# FilamentRecycle.net
KiCad netlist of a schematic drawn in EAGLE
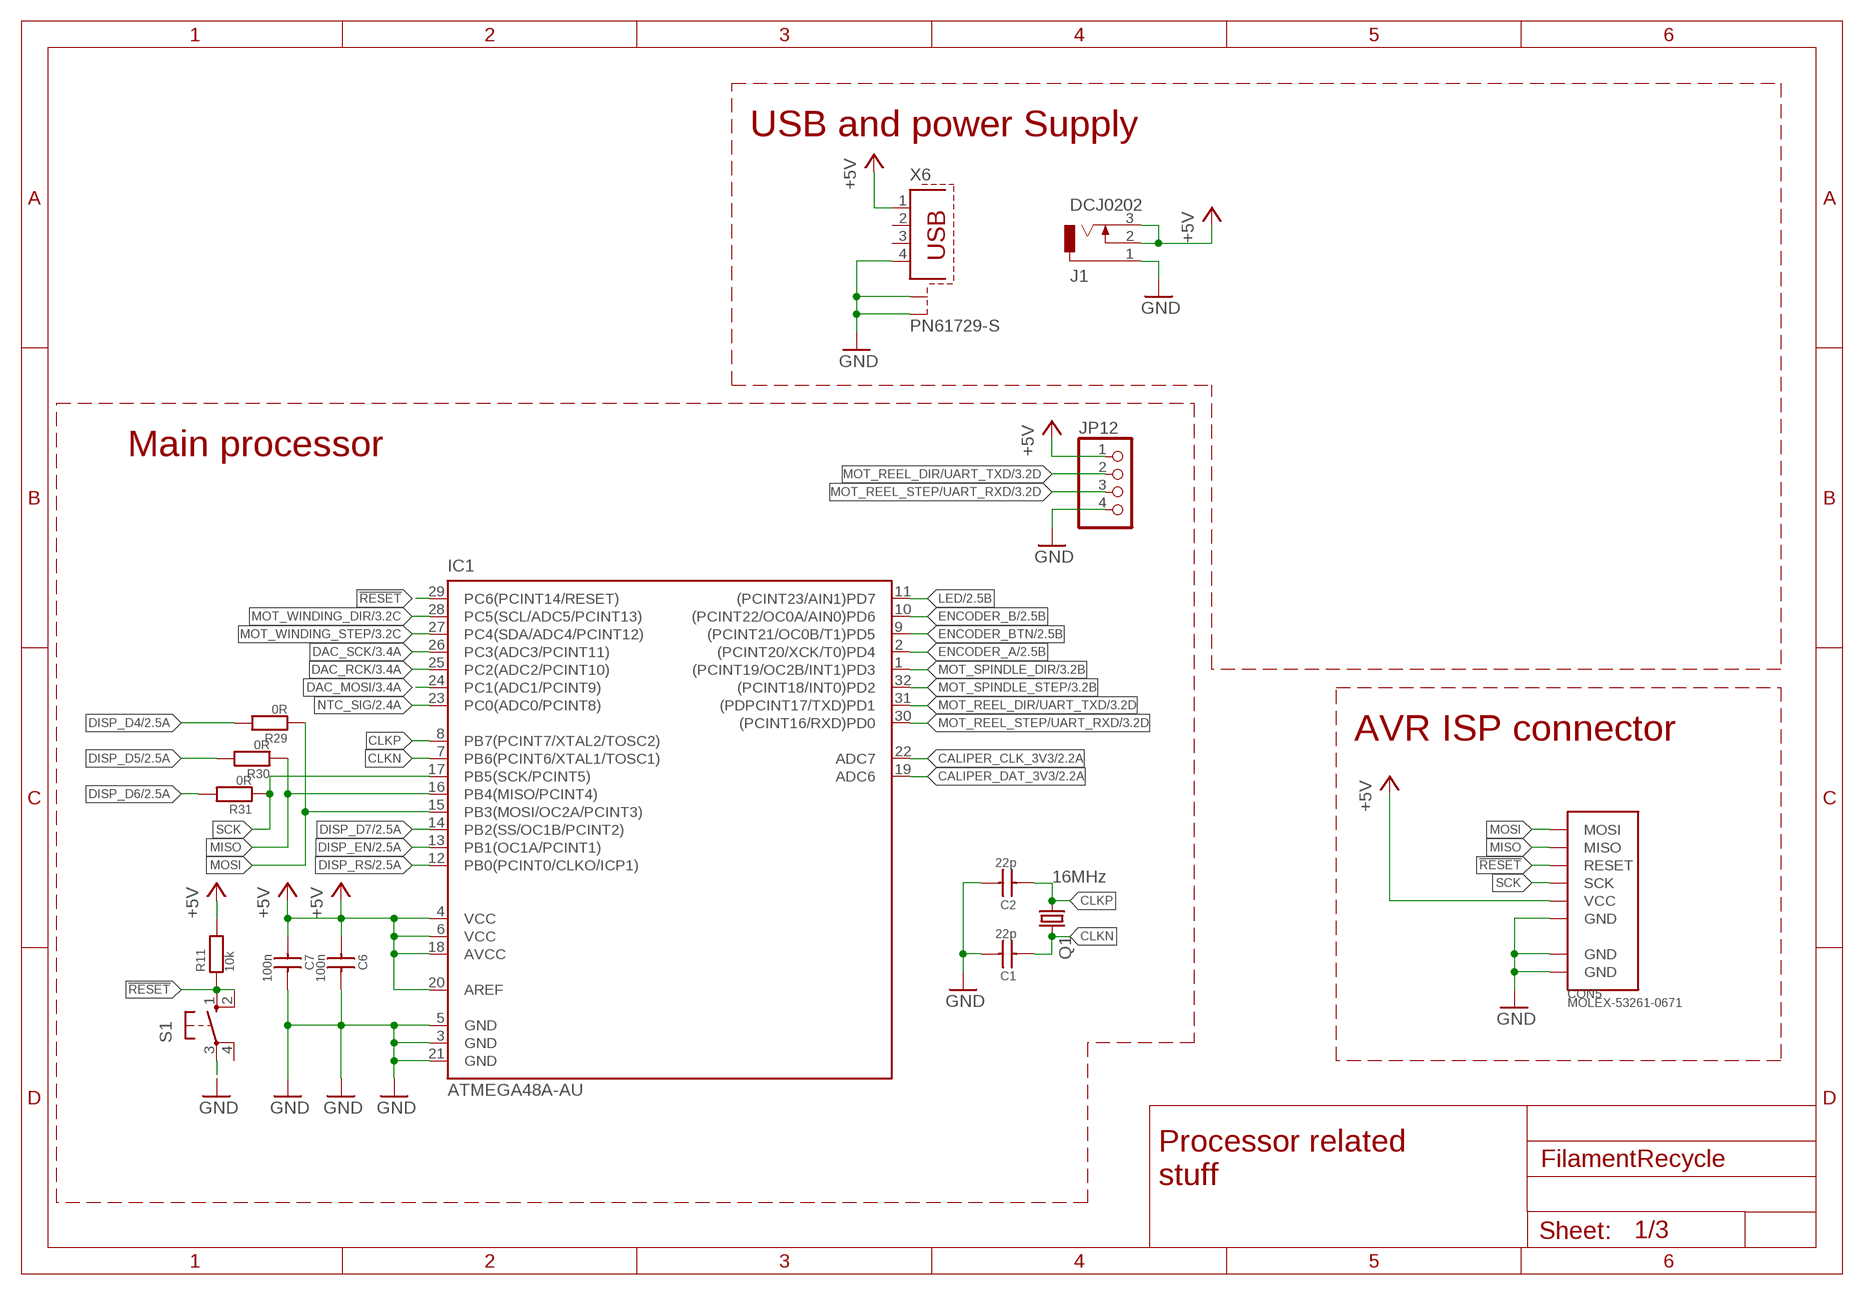
[diagram p0: schematic, sheet 1]
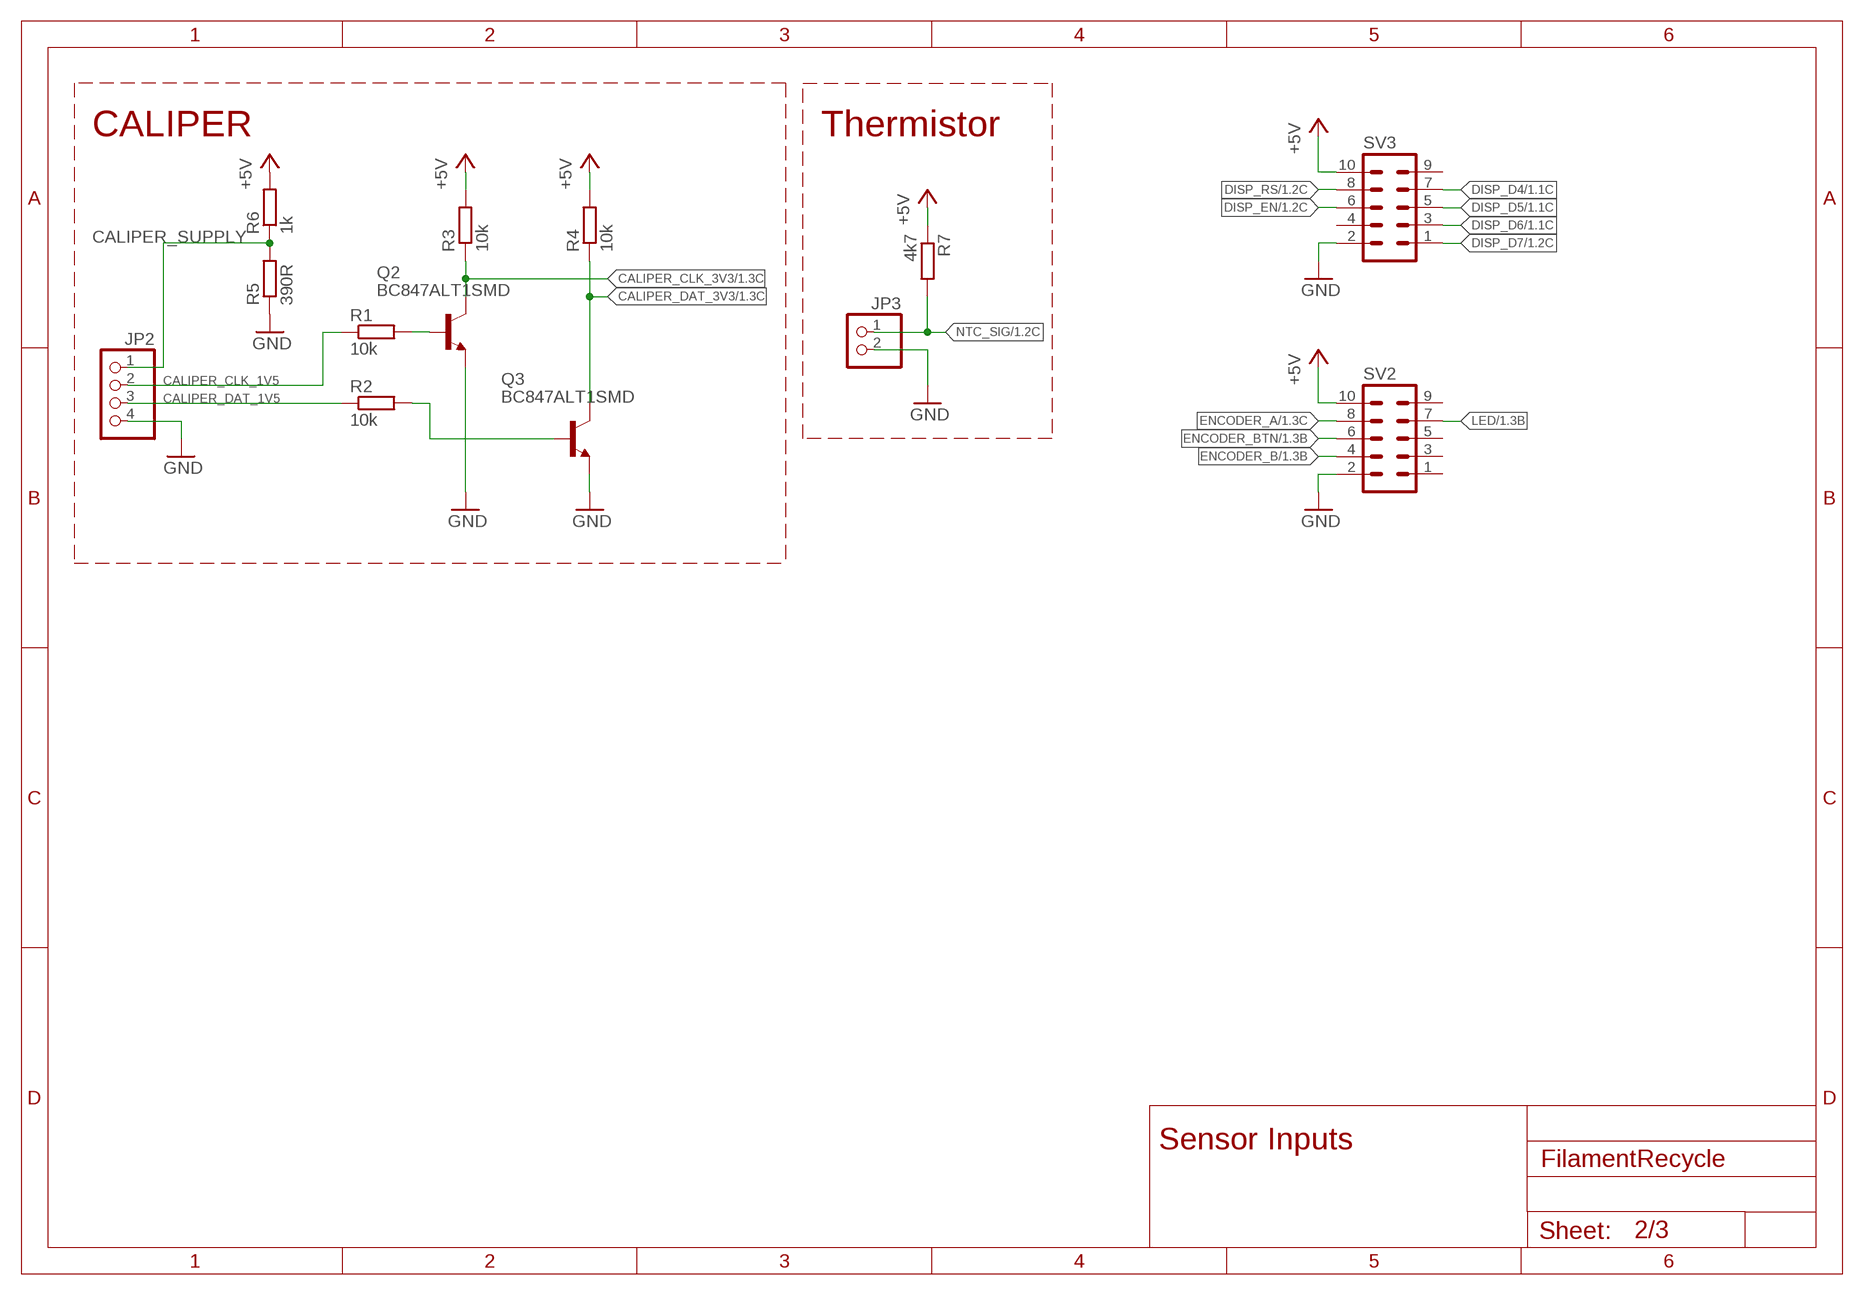
[diagram p1: schematic, sheet 2]
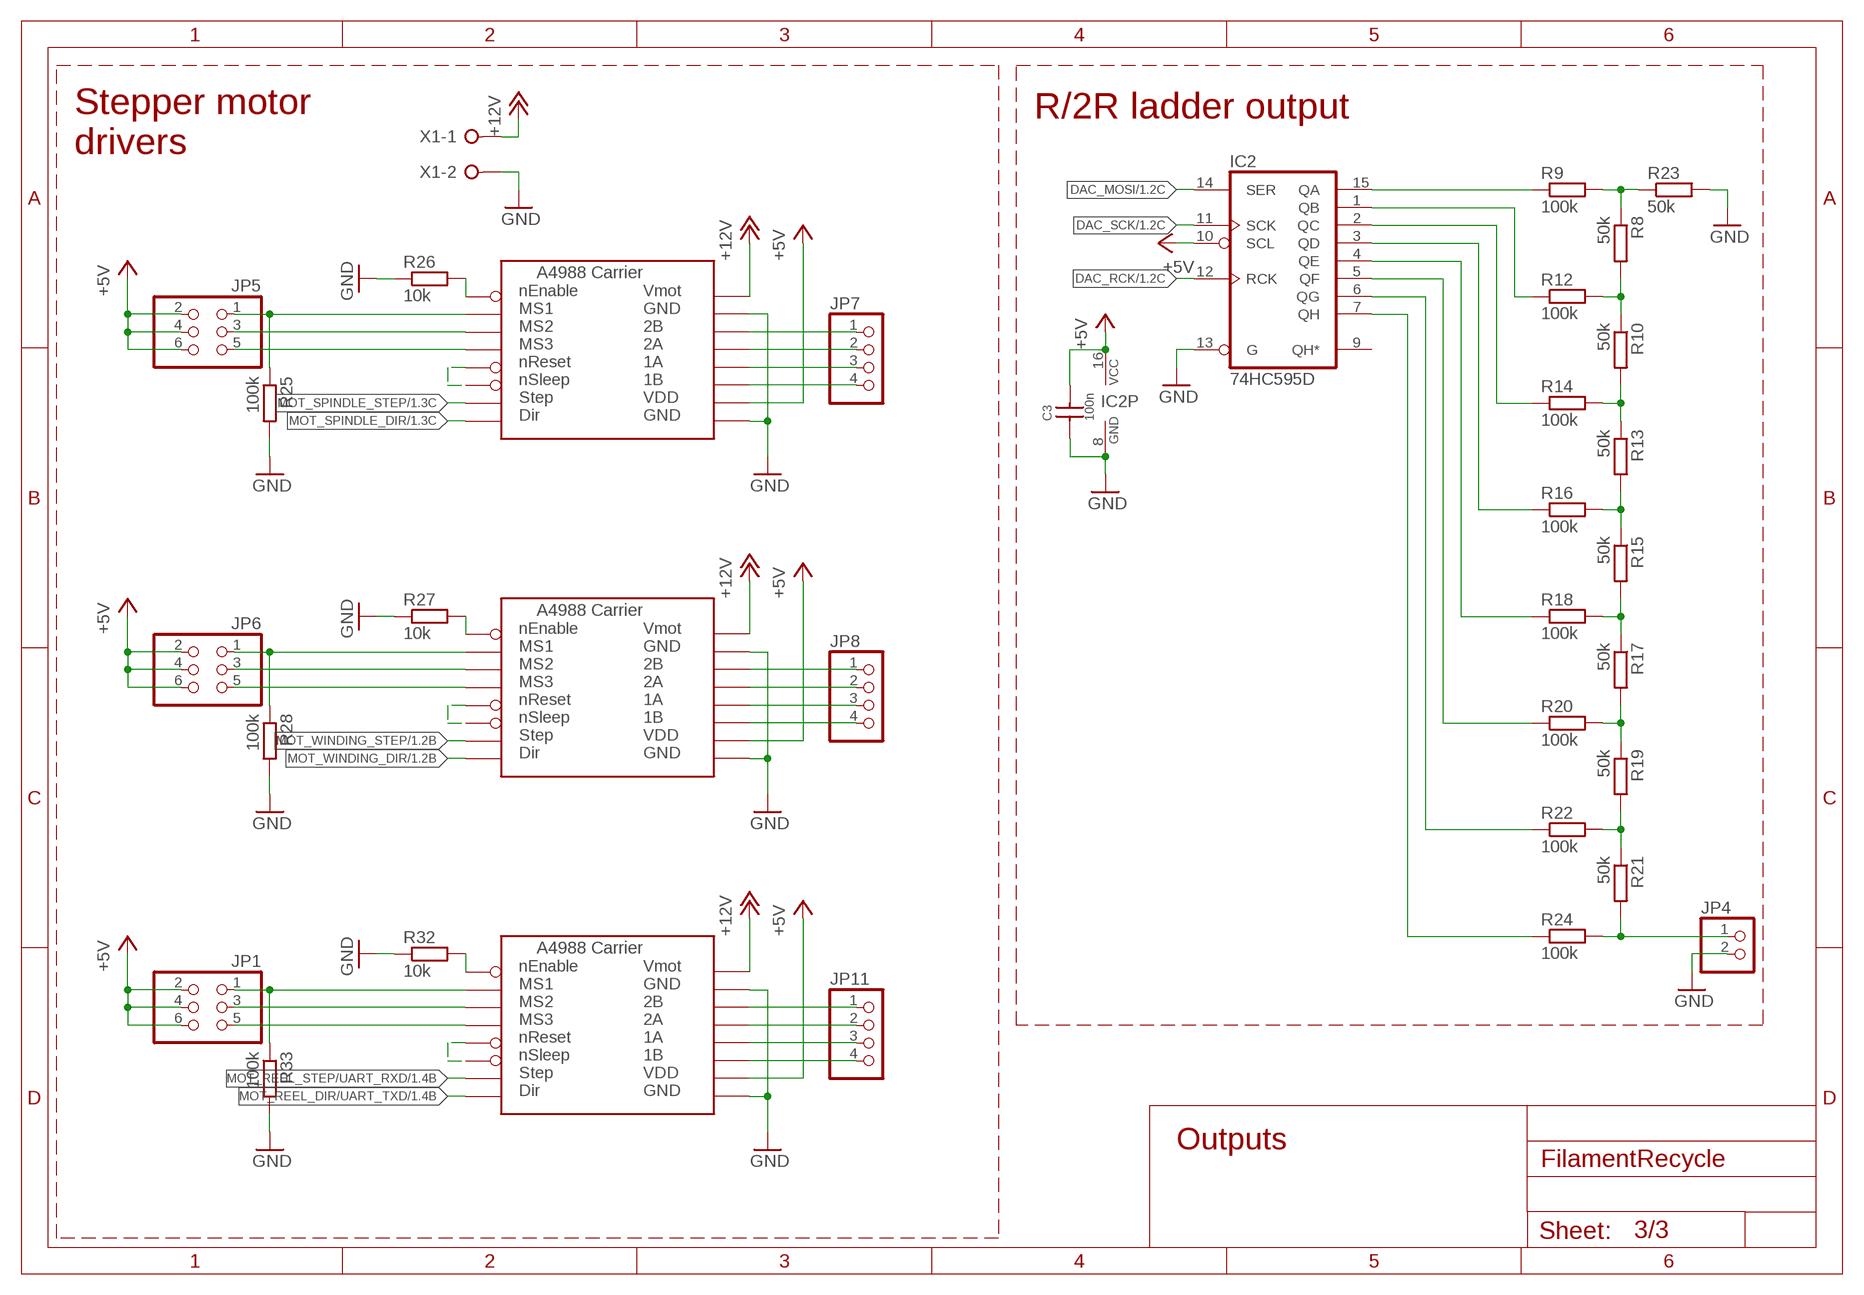
[diagram p2: schematic, sheet 3]

(export (version "E")
  (design (tool "Eeschema 10.0.6"))
  (components
    (comp (ref "C1")
      (value "22p")
      (footprint "eagle-import:C0603")
      (libsource (lib "eagle-import") (part "C_SMD0603"))
    )
    (comp (ref "C2")
      (value "22p")
      (footprint "eagle-import:C0603")
      (libsource (lib "eagle-import") (part "C_SMD0603"))
    )
    (comp (ref "C6")
      (value "100n")
      (footprint "eagle-import:C0603")
      (libsource (lib "eagle-import") (part "C_SMD0603"))
    )
    (comp (ref "C7")
      (value "100n")
      (footprint "eagle-import:C0603")
      (libsource (lib "eagle-import") (part "C_SMD0603"))
    )
    (comp (ref "CON5")
      (value "MOLEX-53261-0671")
      (footprint "eagle-import:MOLEX-53261-0671")
      (libsource (lib "eagle-import") (part "MOLEX-53261-0671"))
    )
    (comp (ref "IC1")
      (value "ATMEGA48A-AU")
      (footprint "eagle-import:TQFP32")
      (libsource (lib "eagle-import") (part "ATMEGA48A-AU"))
    )
    (comp (ref "J1")
      (value "DCJ0202")
      (footprint "eagle-import:DCJ0202")
      (libsource (lib "eagle-import") (part "DCJ0202"))
    )
    (comp (ref "JP12")
      (value "PINHD-1X4")
      (footprint "eagle-import:1X04")
      (libsource (lib "eagle-import") (part "PINHD-1X4"))
    )
    (comp (ref "Q1")
      (value "16MHz")
      (footprint "eagle-import:HC49UP")
      (libsource (lib "eagle-import") (part "CRYSTALHC49UP"))
    )
    (comp (ref "R11")
      (value "10k")
      (footprint "eagle-import:R0603")
      (libsource (lib "eagle-import") (part "R0603"))
    )
    (comp (ref "R29")
      (value "0R")
      (footprint "eagle-import:R0603")
      (libsource (lib "eagle-import") (part "R0603"))
    )
    (comp (ref "R30")
      (value "0R")
      (footprint "eagle-import:R0603")
      (libsource (lib "eagle-import") (part "R0603"))
    )
    (comp (ref "R31")
      (value "0R")
      (footprint "eagle-import:R0603")
      (libsource (lib "eagle-import") (part "R0603"))
    )
    (comp (ref "S1")
      (value "10-XX")
      (footprint "eagle-import:B3F-10XX")
      (fields (field (name "MPN") "B3F-1000"))
      (libsource (lib "eagle-import") (part "10-XX"))
    )
    (comp (ref "X6")
      (value "PN61729-S")
      (footprint "eagle-import:PN61729-S")
      (libsource (lib "eagle-import") (part "PN61729-S"))
    )
    (comp (ref "JP2")
      (value "PINHD-1X4")
      (footprint "eagle-import:1X04")
      (libsource (lib "eagle-import") (part "PINHD-1X4"))
    )
    (comp (ref "JP3")
      (value "PINHD-1X2")
      (footprint "eagle-import:1X02")
      (libsource (lib "eagle-import") (part "PINHD-1X2"))
    )
    (comp (ref "Q2")
      (value "BC847ALT1SMD")
      (footprint "eagle-import:SOT23")
      (libsource (lib "eagle-import") (part "BC847SMDALT1"))
    )
    (comp (ref "Q3")
      (value "BC847ALT1SMD")
      (footprint "eagle-import:SOT23")
      (libsource (lib "eagle-import") (part "BC847SMDALT1"))
    )
    (comp (ref "R1")
      (value "10k")
      (footprint "eagle-import:R0603")
      (libsource (lib "eagle-import") (part "R-EU_R0603"))
    )
    (comp (ref "R2")
      (value "10k")
      (footprint "eagle-import:R0603")
      (libsource (lib "eagle-import") (part "R-EU_R0603"))
    )
    (comp (ref "R3")
      (value "10k")
      (footprint "eagle-import:R0603")
      (libsource (lib "eagle-import") (part "R-EU_R0603"))
    )
    (comp (ref "R4")
      (value "10k")
      (footprint "eagle-import:R0603")
      (libsource (lib "eagle-import") (part "R-EU_R0603"))
    )
    (comp (ref "R5")
      (value "390R")
      (footprint "eagle-import:R0603")
      (libsource (lib "eagle-import") (part "R-EU_R0603"))
    )
    (comp (ref "R6")
      (value "1k")
      (footprint "eagle-import:R0603")
      (libsource (lib "eagle-import") (part "R-EU_R0603"))
    )
    (comp (ref "R7")
      (value "4k7")
      (footprint "eagle-import:R0603")
      (libsource (lib "eagle-import") (part "R-EU_R0603"))
    )
    (comp (ref "SV2")
      (value "ML10")
      (footprint "eagle-import:ML10")
      (libsource (lib "eagle-import") (part "ML10"))
    )
    (comp (ref "SV3")
      (value "ML10")
      (footprint "eagle-import:ML10")
      (libsource (lib "eagle-import") (part "ML10"))
    )
    (comp (ref "C3")
      (value "100n")
      (footprint "eagle-import:C0603")
      (libsource (lib "eagle-import") (part "C_SMD0603"))
    )
    (comp (ref "IC2")
      (value "74HC595D")
      (footprint "eagle-import:SO16")
      (libsource (lib "eagle-import") (part "74595DHC"))
    )
    (comp (ref "JP1")
      (value "PINHD-2X3")
      (footprint "eagle-import:2X03")
      (libsource (lib "eagle-import") (part "PINHD-2X3"))
    )
    (comp (ref "JP4")
      (value "PINHD-1X2")
      (footprint "eagle-import:1X02")
      (libsource (lib "eagle-import") (part "PINHD-1X2"))
    )
    (comp (ref "JP5")
      (value "PINHD-2X3")
      (footprint "eagle-import:2X03")
      (libsource (lib "eagle-import") (part "PINHD-2X3"))
    )
    (comp (ref "JP6")
      (value "PINHD-2X3")
      (footprint "eagle-import:2X03")
      (libsource (lib "eagle-import") (part "PINHD-2X3"))
    )
    (comp (ref "JP7")
      (value "PINHD-1X4")
      (footprint "eagle-import:1X04")
      (libsource (lib "eagle-import") (part "PINHD-1X4"))
    )
    (comp (ref "JP8")
      (value "PINHD-1X4")
      (footprint "eagle-import:1X04")
      (libsource (lib "eagle-import") (part "PINHD-1X4"))
    )
    (comp (ref "JP11")
      (value "PINHD-1X4")
      (footprint "eagle-import:1X04")
      (libsource (lib "eagle-import") (part "PINHD-1X4"))
    )
    (comp (ref "R8")
      (value "50k")
      (footprint "eagle-import:R0603")
      (libsource (lib "eagle-import") (part "R-EU_R0603"))
    )
    (comp (ref "R9")
      (value "100k")
      (footprint "eagle-import:R0603")
      (libsource (lib "eagle-import") (part "R-EU_R0603"))
    )
    (comp (ref "R10")
      (value "50k")
      (footprint "eagle-import:R0603")
      (libsource (lib "eagle-import") (part "R-EU_R0603"))
    )
    (comp (ref "R12")
      (value "100k")
      (footprint "eagle-import:R0603")
      (libsource (lib "eagle-import") (part "R-EU_R0603"))
    )
    (comp (ref "R13")
      (value "50k")
      (footprint "eagle-import:R0603")
      (libsource (lib "eagle-import") (part "R-EU_R0603"))
    )
    (comp (ref "R14")
      (value "100k")
      (footprint "eagle-import:R0603")
      (libsource (lib "eagle-import") (part "R-EU_R0603"))
    )
    (comp (ref "R15")
      (value "50k")
      (footprint "eagle-import:R0603")
      (libsource (lib "eagle-import") (part "R-EU_R0603"))
    )
    (comp (ref "R16")
      (value "100k")
      (footprint "eagle-import:R0603")
      (libsource (lib "eagle-import") (part "R-EU_R0603"))
    )
    (comp (ref "R17")
      (value "50k")
      (footprint "eagle-import:R0603")
      (libsource (lib "eagle-import") (part "R-EU_R0603"))
    )
    (comp (ref "R18")
      (value "100k")
      (footprint "eagle-import:R0603")
      (libsource (lib "eagle-import") (part "R-EU_R0603"))
    )
    (comp (ref "R19")
      (value "50k")
      (footprint "eagle-import:R0603")
      (libsource (lib "eagle-import") (part "R-EU_R0603"))
    )
    (comp (ref "R20")
      (value "100k")
      (footprint "eagle-import:R0603")
      (libsource (lib "eagle-import") (part "R-EU_R0603"))
    )
    (comp (ref "R21")
      (value "50k")
      (footprint "eagle-import:R0603")
      (libsource (lib "eagle-import") (part "R-EU_R0603"))
    )
    (comp (ref "R22")
      (value "100k")
      (footprint "eagle-import:R0603")
      (libsource (lib "eagle-import") (part "R-EU_R0603"))
    )
    (comp (ref "R23")
      (value "50k")
      (footprint "eagle-import:R0603")
      (libsource (lib "eagle-import") (part "R-EU_R0603"))
    )
    (comp (ref "R24")
      (value "100k")
      (footprint "eagle-import:R0603")
      (libsource (lib "eagle-import") (part "R-EU_R0603"))
    )
    (comp (ref "R25")
      (value "100k")
      (footprint "eagle-import:R0603")
      (libsource (lib "eagle-import") (part "R-EU_R0603"))
    )
    (comp (ref "R26")
      (value "10k")
      (footprint "eagle-import:R0603")
      (libsource (lib "eagle-import") (part "R-EU_R0603"))
    )
    (comp (ref "R27")
      (value "10k")
      (footprint "eagle-import:R0603")
      (libsource (lib "eagle-import") (part "R-EU_R0603"))
    )
    (comp (ref "R28")
      (value "100k")
      (footprint "eagle-import:R0603")
      (libsource (lib "eagle-import") (part "R-EU_R0603"))
    )
    (comp (ref "R32")
      (value "10k")
      (footprint "eagle-import:R0603")
      (libsource (lib "eagle-import") (part "R-EU_R0603"))
    )
    (comp (ref "R33")
      (value "100k")
      (footprint "eagle-import:R0603")
      (libsource (lib "eagle-import") (part "R-EU_R0603"))
    )
    (comp (ref "U$7")
      (value "A4988BREAKOUT")
      (footprint "eagle-import:A4988BREAKOUT")
      (libsource (lib "eagle-import") (part "A4988BREAKOUT"))
    )
    (comp (ref "U$9")
      (value "A4988BREAKOUT")
      (footprint "eagle-import:A4988BREAKOUT")
      (libsource (lib "eagle-import") (part "A4988BREAKOUT"))
    )
    (comp (ref "U$14")
      (value "A4988BREAKOUT")
      (footprint "eagle-import:A4988BREAKOUT")
      (libsource (lib "eagle-import") (part "A4988BREAKOUT"))
    )
    (comp (ref "X1")
      (value "W237-02P")
      (footprint "eagle-import:W237-132")
      (libsource (lib "eagle-import") (part "W237-02P"))
    )
  )
  (nets
    (net (code "1") (name "+5V") (class "Default")
      (node (ref "C3") (pin "2") (pinfunction "P$2_2") (pintype "passive"))
      (node (ref "C6") (pin "1") (pinfunction "P$1_1") (pintype "passive"))
      (node (ref "C7") (pin "1") (pinfunction "P$1_1") (pintype "passive"))
      (node (ref "CON5") (pin "5") (pinfunction "VCC_5") (pintype "bidirectional"))
      (node (ref "IC1") (pin "18") (pinfunction "AVCC_18") (pintype "power_in"))
      (node (ref "IC1") (pin "20") (pinfunction "AREF_20") (pintype "power_in"))
      (node (ref "IC1") (pin "4") (pinfunction "VCC_4") (pintype "power_in"))
      (node (ref "IC1") (pin "6") (pinfunction "VCC_6") (pintype "power_in"))
      (node (ref "IC2") (pin "10") (pinfunction "SCL_10") (pintype "input"))
      (node (ref "IC2") (pin "16") (pinfunction "VCC_16") (pintype "power_in"))
      (node (ref "J1") (pin "2") (pinfunction "2_2") (pintype "passive"))
      (node (ref "J1") (pin "3") (pinfunction "3_3") (pintype "passive"))
      (node (ref "JP1") (pin "2") (pinfunction "2_2") (pintype "passive"))
      (node (ref "JP1") (pin "4") (pinfunction "4_4") (pintype "passive"))
      (node (ref "JP1") (pin "6") (pinfunction "6_6") (pintype "passive"))
      (node (ref "JP12") (pin "1") (pinfunction "1_1") (pintype "passive"))
      (node (ref "JP5") (pin "2") (pinfunction "2_2") (pintype "passive"))
      (node (ref "JP5") (pin "4") (pinfunction "4_4") (pintype "passive"))
      (node (ref "JP5") (pin "6") (pinfunction "6_6") (pintype "passive"))
      (node (ref "JP6") (pin "2") (pinfunction "2_2") (pintype "passive"))
      (node (ref "JP6") (pin "4") (pinfunction "4_4") (pintype "passive"))
      (node (ref "JP6") (pin "6") (pinfunction "6_6") (pintype "passive"))
      (node (ref "R11") (pin "2") (pinfunction "P$2_2") (pintype "passive"))
      (node (ref "R3") (pin "2") (pinfunction "2_2") (pintype "passive"))
      (node (ref "R4") (pin "2") (pinfunction "2_2") (pintype "passive"))
      (node (ref "R6") (pin "2") (pinfunction "2_2") (pintype "passive"))
      (node (ref "R7") (pin "1") (pinfunction "1_1") (pintype "passive"))
      (node (ref "SV2") (pin "10") (pinfunction "10_10") (pintype "passive"))
      (node (ref "SV3") (pin "10") (pinfunction "10_10") (pintype "passive"))
      (node (ref "U$14") (pin "VDD") (pinfunction "VDD_VDD") (pintype "power_in"))
      (node (ref "U$7") (pin "VDD") (pinfunction "VDD_VDD") (pintype "power_in"))
      (node (ref "U$9") (pin "VDD") (pinfunction "VDD_VDD") (pintype "power_in"))
      (node (ref "X6") (pin "1") (pinfunction "1_1") (pintype "passive"))
    )
    (net (code "2") (name "+12V") (class "Default")
      (node (ref "U$14") (pin "VMOT") (pinfunction "VMOT_VMOT") (pintype "power_in"))
      (node (ref "U$7") (pin "VMOT") (pinfunction "VMOT_VMOT") (pintype "power_in"))
      (node (ref "U$9") (pin "VMOT") (pinfunction "VMOT_VMOT") (pintype "power_in"))
      (node (ref "X1") (pin "1") (pinfunction "KL_1") (pintype "passive"))
    )
    (net (code "3") (name "CALIPER_CLK_1V5") (class "Default")
      (node (ref "JP2") (pin "2") (pinfunction "2_2") (pintype "passive"))
      (node (ref "R1") (pin "1") (pinfunction "1_1") (pintype "passive"))
    )
    (net (code "4") (name "CALIPER_CLK_3V3") (class "Default")
      (node (ref "IC1") (pin "22") (pinfunction "ADC7_22") (pintype "bidirectional"))
      (node (ref "Q2") (pin "3") (pinfunction "C_3") (pintype "passive"))
      (node (ref "R3") (pin "1") (pinfunction "1_1") (pintype "passive"))
    )
    (net (code "5") (name "CALIPER_DAT_1V5") (class "Default")
      (node (ref "JP2") (pin "3") (pinfunction "3_3") (pintype "passive"))
      (node (ref "R2") (pin "1") (pinfunction "1_1") (pintype "passive"))
    )
    (net (code "6") (name "CALIPER_DAT_3V3") (class "Default")
      (node (ref "IC1") (pin "19") (pinfunction "ADC6_19") (pintype "bidirectional"))
      (node (ref "Q3") (pin "3") (pinfunction "C_3") (pintype "passive"))
      (node (ref "R4") (pin "1") (pinfunction "1_1") (pintype "passive"))
    )
    (net (code "7") (name "CALIPER_SUPPLY") (class "Default")
      (node (ref "JP2") (pin "1") (pinfunction "1_1") (pintype "passive"))
      (node (ref "R5") (pin "2") (pinfunction "2_2") (pintype "passive"))
      (node (ref "R6") (pin "1") (pinfunction "1_1") (pintype "passive"))
    )
    (net (code "8") (name "CLKN") (class "Default")
      (node (ref "C1") (pin "1") (pinfunction "P$1_1") (pintype "passive"))
      (node (ref "IC1") (pin "7") (pinfunction "PB6(PCINT6/XTAL1/TOSC1)_7") (pintype "bidirectional"))
      (node (ref "Q1") (pin "2") (pinfunction "2_2") (pintype "passive"))
    )
    (net (code "9") (name "CLKP") (class "Default")
      (node (ref "C2") (pin "1") (pinfunction "P$1_1") (pintype "passive"))
      (node (ref "IC1") (pin "8") (pinfunction "PB7(PCINT7/XTAL2/TOSC2)_8") (pintype "bidirectional"))
      (node (ref "Q1") (pin "1") (pinfunction "1_1") (pintype "passive"))
    )
    (net (code "10") (name "DAC_MOSI") (class "Default")
      (node (ref "IC1") (pin "24") (pinfunction "PC1(ADC1/PCINT9)_24") (pintype "bidirectional"))
      (node (ref "IC2") (pin "14") (pinfunction "SER_14") (pintype "input"))
    )
    (net (code "11") (name "DAC_RCK") (class "Default")
      (node (ref "IC1") (pin "25") (pinfunction "PC2(ADC2/PCINT10)_25") (pintype "bidirectional"))
      (node (ref "IC2") (pin "12") (pinfunction "RCK_12") (pintype "input"))
    )
    (net (code "12") (name "DAC_SCK") (class "Default")
      (node (ref "IC1") (pin "26") (pinfunction "PC3(ADC3/PCINT11)_26") (pintype "bidirectional"))
      (node (ref "IC2") (pin "11") (pinfunction "SCK_11") (pintype "input"))
    )
    (net (code "13") (name "DISP_D4") (class "Default")
      (node (ref "R29") (pin "2") (pinfunction "P$2_2") (pintype "passive"))
      (node (ref "SV3") (pin "7") (pinfunction "7_7") (pintype "passive"))
    )
    (net (code "14") (name "DISP_D5") (class "Default")
      (node (ref "R30") (pin "2") (pinfunction "P$2_2") (pintype "passive"))
      (node (ref "SV3") (pin "5") (pinfunction "5_5") (pintype "passive"))
    )
    (net (code "15") (name "DISP_D6") (class "Default")
      (node (ref "R31") (pin "2") (pinfunction "P$2_2") (pintype "passive"))
      (node (ref "SV3") (pin "3") (pinfunction "3_3") (pintype "passive"))
    )
    (net (code "16") (name "DISP_D7") (class "Default")
      (node (ref "IC1") (pin "14") (pinfunction "PB2(SS/OC1B/PCINT2)_14") (pintype "bidirectional"))
      (node (ref "SV3") (pin "1") (pinfunction "1_1") (pintype "passive"))
    )
    (net (code "17") (name "DISP_EN") (class "Default")
      (node (ref "IC1") (pin "13") (pinfunction "PB1(OC1A/PCINT1)_13") (pintype "bidirectional"))
      (node (ref "SV3") (pin "6") (pinfunction "6_6") (pintype "passive"))
    )
    (net (code "18") (name "DISP_RS") (class "Default")
      (node (ref "IC1") (pin "12") (pinfunction "PB0(PCINT0/CLKO/ICP1)_12") (pintype "bidirectional"))
      (node (ref "SV3") (pin "8") (pinfunction "8_8") (pintype "passive"))
    )
    (net (code "19") (name "ENCODER_A") (class "Default")
      (node (ref "IC1") (pin "2") (pinfunction "(PCINT20/XCK/T0)PD4_2") (pintype "bidirectional"))
      (node (ref "SV2") (pin "8") (pinfunction "8_8") (pintype "passive"))
    )
    (net (code "20") (name "ENCODER_B") (class "Default")
      (node (ref "IC1") (pin "10") (pinfunction "(PCINT22/OC0A/AIN0)PD6_10") (pintype "bidirectional"))
      (node (ref "SV2") (pin "4") (pinfunction "4_4") (pintype "passive"))
    )
    (net (code "21") (name "ENCODER_BTN") (class "Default")
      (node (ref "IC1") (pin "9") (pinfunction "(PCINT21/OC0B/T1)PD5_9") (pintype "bidirectional"))
      (node (ref "SV2") (pin "6") (pinfunction "6_6") (pintype "passive"))
    )
    (net (code "22") (name "GND") (class "Default")
      (node (ref "C1") (pin "2") (pinfunction "P$2_2") (pintype "passive"))
      (node (ref "C2") (pin "2") (pinfunction "P$2_2") (pintype "passive"))
      (node (ref "C3") (pin "1") (pinfunction "P$1_1") (pintype "passive"))
      (node (ref "C6") (pin "2") (pinfunction "P$2_2") (pintype "passive"))
      (node (ref "C7") (pin "2") (pinfunction "P$2_2") (pintype "passive"))
      (node (ref "CON5") (pin "6") (pinfunction "GND_6") (pintype "bidirectional"))
      (node (ref "CON5") (pin "GND@1") (pinfunction "GND_GND@1") (pintype "power_in"))
      (node (ref "CON5") (pin "GND@2") (pinfunction "GND_GND@2") (pintype "power_in"))
      (node (ref "IC1") (pin "21") (pinfunction "GND_21") (pintype "power_in"))
      (node (ref "IC1") (pin "3") (pinfunction "GND_3") (pintype "power_in"))
      (node (ref "IC1") (pin "5") (pinfunction "GND_5") (pintype "power_in"))
      (node (ref "IC2") (pin "13") (pinfunction "G_13") (pintype "input"))
      (node (ref "IC2") (pin "8") (pinfunction "GND_8") (pintype "power_in"))
      (node (ref "J1") (pin "1") (pinfunction "1_1") (pintype "passive"))
      (node (ref "JP12") (pin "4") (pinfunction "4_4") (pintype "passive"))
      (node (ref "JP2") (pin "4") (pinfunction "4_4") (pintype "passive"))
      (node (ref "JP3") (pin "2") (pinfunction "2_2") (pintype "passive"))
      (node (ref "JP4") (pin "2") (pinfunction "2_2") (pintype "passive"))
      (node (ref "Q2") (pin "2") (pinfunction "E_2") (pintype "passive"))
      (node (ref "Q3") (pin "2") (pinfunction "E_2") (pintype "passive"))
      (node (ref "R23") (pin "2") (pinfunction "2_2") (pintype "passive"))
      (node (ref "R25") (pin "2") (pinfunction "2_2") (pintype "passive"))
      (node (ref "R26") (pin "1") (pinfunction "1_1") (pintype "passive"))
      (node (ref "R27") (pin "1") (pinfunction "1_1") (pintype "passive"))
      (node (ref "R28") (pin "2") (pinfunction "2_2") (pintype "passive"))
      (node (ref "R32") (pin "1") (pinfunction "1_1") (pintype "passive"))
      (node (ref "R33") (pin "2") (pinfunction "2_2") (pintype "passive"))
      (node (ref "R5") (pin "1") (pinfunction "1_1") (pintype "passive"))
      (node (ref "S1") (pin "3") (pinfunction "P_3") (pintype "passive"))
      (node (ref "SV2") (pin "2") (pinfunction "2_2") (pintype "passive"))
      (node (ref "SV3") (pin "2") (pinfunction "2_2") (pintype "passive"))
      (node (ref "U$14") (pin "GND@0") (pinfunction "GND_GND@0") (pintype "power_in"))
      (node (ref "U$14") (pin "GND@1") (pinfunction "GND_GND@1") (pintype "power_in"))
      (node (ref "U$7") (pin "GND@0") (pinfunction "GND_GND@0") (pintype "power_in"))
      (node (ref "U$7") (pin "GND@1") (pinfunction "GND_GND@1") (pintype "power_in"))
      (node (ref "U$9") (pin "GND@0") (pinfunction "GND_GND@0") (pintype "power_in"))
      (node (ref "U$9") (pin "GND@1") (pinfunction "GND_GND@1") (pintype "power_in"))
      (node (ref "X1") (pin "2") (pinfunction "KL_2") (pintype "passive"))
      (node (ref "X6") (pin "4") (pinfunction "4_4") (pintype "passive"))
      (node (ref "X6") (pin "S1") (pinfunction "S1_S1") (pintype "passive"))
      (node (ref "X6") (pin "S2") (pinfunction "S2_S2") (pintype "passive"))
    )
    (net (code "23") (name "LED") (class "Default")
      (node (ref "IC1") (pin "11") (pinfunction "(PCINT23/AIN1)PD7_11") (pintype "bidirectional"))
      (node (ref "SV2") (pin "7") (pinfunction "7_7") (pintype "passive"))
    )
    (net (code "24") (name "MISO") (class "Default")
      (node (ref "CON5") (pin "2") (pinfunction "MISO_2") (pintype "bidirectional"))
      (node (ref "IC1") (pin "16") (pinfunction "PB4(MISO/PCINT4)_16") (pintype "bidirectional"))
      (node (ref "R30") (pin "1") (pinfunction "P$1_1") (pintype "passive"))
    )
    (net (code "25") (name "MOSI") (class "Default")
      (node (ref "CON5") (pin "1") (pinfunction "MOSI_1") (pintype "bidirectional"))
      (node (ref "IC1") (pin "15") (pinfunction "PB3(MOSI/OC2A/PCINT3)_15") (pintype "bidirectional"))
      (node (ref "R29") (pin "1") (pinfunction "P$1_1") (pintype "passive"))
    )
    (net (code "26") (name "MOT_REEL_DIR{slash}UART_TXD") (class "Default")
      (node (ref "IC1") (pin "31") (pinfunction "(PDPCINT17/TXD)PD1_31") (pintype "bidirectional"))
      (node (ref "JP12") (pin "2") (pinfunction "2_2") (pintype "passive"))
      (node (ref "U$9") (pin "DIR") (pinfunction "DIR_DIR") (pintype "input"))
    )
    (net (code "27") (name "MOT_REEL_STEP{slash}UART_RXD") (class "Default")
      (node (ref "IC1") (pin "30") (pinfunction "(PCINT16/RXD)PD0_30") (pintype "bidirectional"))
      (node (ref "JP12") (pin "3") (pinfunction "3_3") (pintype "passive"))
      (node (ref "U$9") (pin "STEP") (pinfunction "STEP_STEP") (pintype "input"))
    )
    (net (code "28") (name "MOT_SPINDLE_DIR") (class "Default")
      (node (ref "IC1") (pin "1") (pinfunction "(PCINT19/OC2B/INT1)PD3_1") (pintype "bidirectional"))
      (node (ref "U$7") (pin "DIR") (pinfunction "DIR_DIR") (pintype "input"))
    )
    (net (code "29") (name "MOT_SPINDLE_STEP") (class "Default")
      (node (ref "IC1") (pin "32") (pinfunction "(PCINT18/INT0)PD2_32") (pintype "bidirectional"))
      (node (ref "U$7") (pin "STEP") (pinfunction "STEP_STEP") (pintype "input"))
    )
    (net (code "30") (name "MOT_WINDING_DIR") (class "Default")
      (node (ref "IC1") (pin "28") (pinfunction "PC5(SCL/ADC5/PCINT13)_28") (pintype "bidirectional"))
      (node (ref "U$14") (pin "DIR") (pinfunction "DIR_DIR") (pintype "input"))
    )
    (net (code "31") (name "MOT_WINDING_STEP") (class "Default")
      (node (ref "IC1") (pin "27") (pinfunction "PC4(SDA/ADC4/PCINT12)_27") (pintype "bidirectional"))
      (node (ref "U$14") (pin "STEP") (pinfunction "STEP_STEP") (pintype "input"))
    )
    (net (code "32") (name "NTC_SIG") (class "Default")
      (node (ref "IC1") (pin "23") (pinfunction "PC0(ADC0/PCINT8)_23") (pintype "bidirectional"))
      (node (ref "JP3") (pin "1") (pinfunction "1_1") (pintype "passive"))
      (node (ref "R7") (pin "2") (pinfunction "2_2") (pintype "passive"))
    )
    (net (code "33") (name "Net-(IC2A-QA)") (class "Default")
      (node (ref "IC2") (pin "15") (pinfunction "QA_15") (pintype "tri_state"))
      (node (ref "R9") (pin "1") (pinfunction "1_1") (pintype "passive"))
    )
    (net (code "34") (name "Net-(IC2A-QB)") (class "Default")
      (node (ref "IC2") (pin "1") (pinfunction "QB_1") (pintype "tri_state"))
      (node (ref "R12") (pin "1") (pinfunction "1_1") (pintype "passive"))
    )
    (net (code "35") (name "Net-(IC2A-QC)") (class "Default")
      (node (ref "IC2") (pin "2") (pinfunction "QC_2") (pintype "tri_state"))
      (node (ref "R14") (pin "1") (pinfunction "1_1") (pintype "passive"))
    )
    (net (code "36") (name "Net-(IC2A-QD)") (class "Default")
      (node (ref "IC2") (pin "3") (pinfunction "QD_3") (pintype "tri_state"))
      (node (ref "R16") (pin "1") (pinfunction "1_1") (pintype "passive"))
    )
    (net (code "37") (name "Net-(IC2A-QE)") (class "Default")
      (node (ref "IC2") (pin "4") (pinfunction "QE_4") (pintype "tri_state"))
      (node (ref "R18") (pin "1") (pinfunction "1_1") (pintype "passive"))
    )
    (net (code "38") (name "Net-(IC2A-QF)") (class "Default")
      (node (ref "IC2") (pin "5") (pinfunction "QF_5") (pintype "tri_state"))
      (node (ref "R20") (pin "1") (pinfunction "1_1") (pintype "passive"))
    )
    (net (code "39") (name "Net-(IC2A-QG)") (class "Default")
      (node (ref "IC2") (pin "6") (pinfunction "QG_6") (pintype "tri_state"))
      (node (ref "R22") (pin "1") (pinfunction "1_1") (pintype "passive"))
    )
    (net (code "40") (name "Net-(IC2A-QH)") (class "Default")
      (node (ref "IC2") (pin "7") (pinfunction "QH_7") (pintype "tri_state"))
      (node (ref "R24") (pin "1") (pinfunction "1_1") (pintype "passive"))
    )
    (net (code "41") (name "Net-(JP1-Pad1)") (class "Default")
      (node (ref "JP1") (pin "1") (pinfunction "1_1") (pintype "passive"))
      (node (ref "R33") (pin "1") (pinfunction "1_1") (pintype "passive"))
      (node (ref "U$9") (pin "MS1") (pinfunction "MS1_MS1") (pintype "input"))
    )
    (net (code "42") (name "Net-(JP1-Pad3)") (class "Default")
      (node (ref "JP1") (pin "3") (pinfunction "3_3") (pintype "passive"))
      (node (ref "U$9") (pin "MS2") (pinfunction "MS2_MS2") (pintype "input"))
    )
    (net (code "43") (name "Net-(JP1-Pad5)") (class "Default")
      (node (ref "JP1") (pin "5") (pinfunction "5_5") (pintype "passive"))
      (node (ref "U$9") (pin "MS3") (pinfunction "MS3_MS3") (pintype "input"))
    )
    (net (code "44") (name "Net-(JP4-Pad1)") (class "Default")
      (node (ref "JP4") (pin "1") (pinfunction "1_1") (pintype "passive"))
      (node (ref "R21") (pin "2") (pinfunction "2_2") (pintype "passive"))
      (node (ref "R24") (pin "2") (pinfunction "2_2") (pintype "passive"))
    )
    (net (code "45") (name "Net-(JP5-Pad1)") (class "Default")
      (node (ref "JP5") (pin "1") (pinfunction "1_1") (pintype "passive"))
      (node (ref "R25") (pin "1") (pinfunction "1_1") (pintype "passive"))
      (node (ref "U$7") (pin "MS1") (pinfunction "MS1_MS1") (pintype "input"))
    )
    (net (code "46") (name "Net-(JP5-Pad3)") (class "Default")
      (node (ref "JP5") (pin "3") (pinfunction "3_3") (pintype "passive"))
      (node (ref "U$7") (pin "MS2") (pinfunction "MS2_MS2") (pintype "input"))
    )
    (net (code "47") (name "Net-(JP5-Pad5)") (class "Default")
      (node (ref "JP5") (pin "5") (pinfunction "5_5") (pintype "passive"))
      (node (ref "U$7") (pin "MS3") (pinfunction "MS3_MS3") (pintype "input"))
    )
    (net (code "48") (name "Net-(JP6-Pad1)") (class "Default")
      (node (ref "JP6") (pin "1") (pinfunction "1_1") (pintype "passive"))
      (node (ref "R28") (pin "1") (pinfunction "1_1") (pintype "passive"))
      (node (ref "U$14") (pin "MS1") (pinfunction "MS1_MS1") (pintype "input"))
    )
    (net (code "49") (name "Net-(JP6-Pad3)") (class "Default")
      (node (ref "JP6") (pin "3") (pinfunction "3_3") (pintype "passive"))
      (node (ref "U$14") (pin "MS2") (pinfunction "MS2_MS2") (pintype "input"))
    )
    (net (code "50") (name "Net-(JP6-Pad5)") (class "Default")
      (node (ref "JP6") (pin "5") (pinfunction "5_5") (pintype "passive"))
      (node (ref "U$14") (pin "MS3") (pinfunction "MS3_MS3") (pintype "input"))
    )
    (net (code "51") (name "Net-(JP7-Pad1)") (class "Default")
      (node (ref "JP7") (pin "1") (pinfunction "1_1") (pintype "passive"))
      (node (ref "U$7") (pin "2B") (pinfunction "2B_2B") (pintype "output"))
    )
    (net (code "52") (name "Net-(JP7-Pad2)") (class "Default")
      (node (ref "JP7") (pin "2") (pinfunction "2_2") (pintype "passive"))
      (node (ref "U$7") (pin "2A") (pinfunction "2A_2A") (pintype "output"))
    )
    (net (code "53") (name "Net-(JP7-Pad3)") (class "Default")
      (node (ref "JP7") (pin "3") (pinfunction "3_3") (pintype "passive"))
      (node (ref "U$7") (pin "1A") (pinfunction "1A_1A") (pintype "output"))
    )
    (net (code "54") (name "Net-(JP7-Pad4)") (class "Default")
      (node (ref "JP7") (pin "4") (pinfunction "4_4") (pintype "passive"))
      (node (ref "U$7") (pin "1B") (pinfunction "1B_1B") (pintype "output"))
    )
    (net (code "55") (name "Net-(JP8-Pad1)") (class "Default")
      (node (ref "JP8") (pin "1") (pinfunction "1_1") (pintype "passive"))
      (node (ref "U$14") (pin "2B") (pinfunction "2B_2B") (pintype "output"))
    )
    (net (code "56") (name "Net-(JP8-Pad2)") (class "Default")
      (node (ref "JP8") (pin "2") (pinfunction "2_2") (pintype "passive"))
      (node (ref "U$14") (pin "2A") (pinfunction "2A_2A") (pintype "output"))
    )
    (net (code "57") (name "Net-(JP8-Pad3)") (class "Default")
      (node (ref "JP8") (pin "3") (pinfunction "3_3") (pintype "passive"))
      (node (ref "U$14") (pin "1A") (pinfunction "1A_1A") (pintype "output"))
    )
    (net (code "58") (name "Net-(JP8-Pad4)") (class "Default")
      (node (ref "JP8") (pin "4") (pinfunction "4_4") (pintype "passive"))
      (node (ref "U$14") (pin "1B") (pinfunction "1B_1B") (pintype "output"))
    )
    (net (code "59") (name "Net-(JP11-Pad1)") (class "Default")
      (node (ref "JP11") (pin "1") (pinfunction "1_1") (pintype "passive"))
      (node (ref "U$9") (pin "2B") (pinfunction "2B_2B") (pintype "output"))
    )
    (net (code "60") (name "Net-(JP11-Pad2)") (class "Default")
      (node (ref "JP11") (pin "2") (pinfunction "2_2") (pintype "passive"))
      (node (ref "U$9") (pin "2A") (pinfunction "2A_2A") (pintype "output"))
    )
    (net (code "61") (name "Net-(JP11-Pad3)") (class "Default")
      (node (ref "JP11") (pin "3") (pinfunction "3_3") (pintype "passive"))
      (node (ref "U$9") (pin "1A") (pinfunction "1A_1A") (pintype "output"))
    )
    (net (code "62") (name "Net-(JP11-Pad4)") (class "Default")
      (node (ref "JP11") (pin "4") (pinfunction "4_4") (pintype "passive"))
      (node (ref "U$9") (pin "1B") (pinfunction "1B_1B") (pintype "output"))
    )
    (net (code "63") (name "Net-(Q2-B)") (class "Default")
      (node (ref "Q2") (pin "1") (pinfunction "B_1") (pintype "passive"))
      (node (ref "R1") (pin "2") (pinfunction "2_2") (pintype "passive"))
    )
    (net (code "64") (name "Net-(Q3-B)") (class "Default")
      (node (ref "Q3") (pin "1") (pinfunction "B_1") (pintype "passive"))
      (node (ref "R2") (pin "2") (pinfunction "2_2") (pintype "passive"))
    )
    (net (code "65") (name "Net-(R10-Pad1)") (class "Default")
      (node (ref "R10") (pin "1") (pinfunction "1_1") (pintype "passive"))
      (node (ref "R12") (pin "2") (pinfunction "2_2") (pintype "passive"))
      (node (ref "R8") (pin "2") (pinfunction "2_2") (pintype "passive"))
    )
    (net (code "66") (name "Net-(R10-Pad2)") (class "Default")
      (node (ref "R10") (pin "2") (pinfunction "2_2") (pintype "passive"))
      (node (ref "R13") (pin "1") (pinfunction "1_1") (pintype "passive"))
      (node (ref "R14") (pin "2") (pinfunction "2_2") (pintype "passive"))
    )
    (net (code "67") (name "Net-(R13-Pad2)") (class "Default")
      (node (ref "R13") (pin "2") (pinfunction "2_2") (pintype "passive"))
      (node (ref "R15") (pin "1") (pinfunction "1_1") (pintype "passive"))
      (node (ref "R16") (pin "2") (pinfunction "2_2") (pintype "passive"))
    )
    (net (code "68") (name "Net-(R15-Pad2)") (class "Default")
      (node (ref "R15") (pin "2") (pinfunction "2_2") (pintype "passive"))
      (node (ref "R17") (pin "1") (pinfunction "1_1") (pintype "passive"))
      (node (ref "R18") (pin "2") (pinfunction "2_2") (pintype "passive"))
    )
    (net (code "69") (name "Net-(R17-Pad2)") (class "Default")
      (node (ref "R17") (pin "2") (pinfunction "2_2") (pintype "passive"))
      (node (ref "R19") (pin "1") (pinfunction "1_1") (pintype "passive"))
      (node (ref "R20") (pin "2") (pinfunction "2_2") (pintype "passive"))
    )
    (net (code "70") (name "Net-(R19-Pad2)") (class "Default")
      (node (ref "R19") (pin "2") (pinfunction "2_2") (pintype "passive"))
      (node (ref "R21") (pin "1") (pinfunction "1_1") (pintype "passive"))
      (node (ref "R22") (pin "2") (pinfunction "2_2") (pintype "passive"))
    )
    (net (code "71") (name "Net-(R23-Pad1)") (class "Default")
      (node (ref "R23") (pin "1") (pinfunction "1_1") (pintype "passive"))
      (node (ref "R8") (pin "1") (pinfunction "1_1") (pintype "passive"))
      (node (ref "R9") (pin "2") (pinfunction "2_2") (pintype "passive"))
    )
    (net (code "72") (name "Net-(R26-Pad2)") (class "Default")
      (node (ref "R26") (pin "2") (pinfunction "2_2") (pintype "passive"))
      (node (ref "U$7") (pin "EN") (pinfunction "EN_EN") (pintype "input"))
    )
    (net (code "73") (name "Net-(R27-Pad2)") (class "Default")
      (node (ref "R27") (pin "2") (pinfunction "2_2") (pintype "passive"))
      (node (ref "U$14") (pin "EN") (pinfunction "EN_EN") (pintype "input"))
    )
    (net (code "74") (name "Net-(R32-Pad2)") (class "Default")
      (node (ref "R32") (pin "2") (pinfunction "2_2") (pintype "passive"))
      (node (ref "U$9") (pin "EN") (pinfunction "EN_EN") (pintype "input"))
    )
    (net (code "75") (name "Net-(U$7-SLEEP)") (class "Default")
      (node (ref "U$7") (pin "RST") (pinfunction "RST_RST") (pintype "input"))
      (node (ref "U$7") (pin "SLP") (pinfunction "SLEEP_SLP") (pintype "input"))
    )
    (net (code "76") (name "Net-(U$9-SLEEP)") (class "Default")
      (node (ref "U$9") (pin "RST") (pinfunction "RST_RST") (pintype "input"))
      (node (ref "U$9") (pin "SLP") (pinfunction "SLEEP_SLP") (pintype "input"))
    )
    (net (code "77") (name "Net-(U$14-SLEEP)") (class "Default")
      (node (ref "U$14") (pin "RST") (pinfunction "RST_RST") (pintype "input"))
      (node (ref "U$14") (pin "SLP") (pinfunction "SLEEP_SLP") (pintype "input"))
    )
    (net (code "78") (name "SCK") (class "Default")
      (node (ref "CON5") (pin "4") (pinfunction "SCK_4") (pintype "bidirectional"))
      (node (ref "IC1") (pin "17") (pinfunction "PB5(SCK/PCINT5)_17") (pintype "bidirectional"))
      (node (ref "R31") (pin "1") (pinfunction "P$1_1") (pintype "passive"))
    )
    (net (code "79") (name "unconnected-(IC2A-QH*-Pad9)") (class "Default")
      (node (ref "IC2") (pin "9") (pinfunction "QH*_9") (pintype "tri_state"))
    )
    (net (code "80") (name "unconnected-(S1-P1-Pad4)") (class "Default")
      (node (ref "S1") (pin "4") (pinfunction "P1_4") (pintype "passive"))
    )
    (net (code "81") (name "unconnected-(SV2-Pad1)") (class "Default")
      (node (ref "SV2") (pin "1") (pinfunction "1_1") (pintype "passive"))
    )
    (net (code "82") (name "unconnected-(SV2-Pad3)") (class "Default")
      (node (ref "SV2") (pin "3") (pinfunction "3_3") (pintype "passive"))
    )
    (net (code "83") (name "unconnected-(SV2-Pad5)") (class "Default")
      (node (ref "SV2") (pin "5") (pinfunction "5_5") (pintype "passive"))
    )
    (net (code "84") (name "unconnected-(SV2-Pad9)") (class "Default")
      (node (ref "SV2") (pin "9") (pinfunction "9_9") (pintype "passive"))
    )
    (net (code "85") (name "unconnected-(SV3-Pad4)") (class "Default")
      (node (ref "SV3") (pin "4") (pinfunction "4_4") (pintype "passive"))
    )
    (net (code "86") (name "unconnected-(SV3-Pad9)") (class "Default")
      (node (ref "SV3") (pin "9") (pinfunction "9_9") (pintype "passive"))
    )
    (net (code "87") (name "unconnected-(X6-Pad2)") (class "Default")
      (node (ref "X6") (pin "2") (pinfunction "2_2") (pintype "passive"))
    )
    (net (code "88") (name "unconnected-(X6-Pad3)") (class "Default")
      (node (ref "X6") (pin "3") (pinfunction "3_3") (pintype "passive"))
    )
    (net (code "89") (name "~{RESET}") (class "Default")
      (node (ref "CON5") (pin "3") (pinfunction "RESET_3") (pintype "bidirectional"))
      (node (ref "IC1") (pin "29") (pinfunction "PC6(PCINT14/RESET)_29") (pintype "bidirectional"))
      (node (ref "R11") (pin "1") (pinfunction "P$1_1") (pintype "passive"))
      (node (ref "S1") (pin "1") (pinfunction "S_1") (pintype "passive"))
      (node (ref "S1") (pin "2") (pinfunction "S1_2") (pintype "passive"))
    )
  )
)
